# Power.net
KiCad netlist of a schematic drawn in Altium Designer
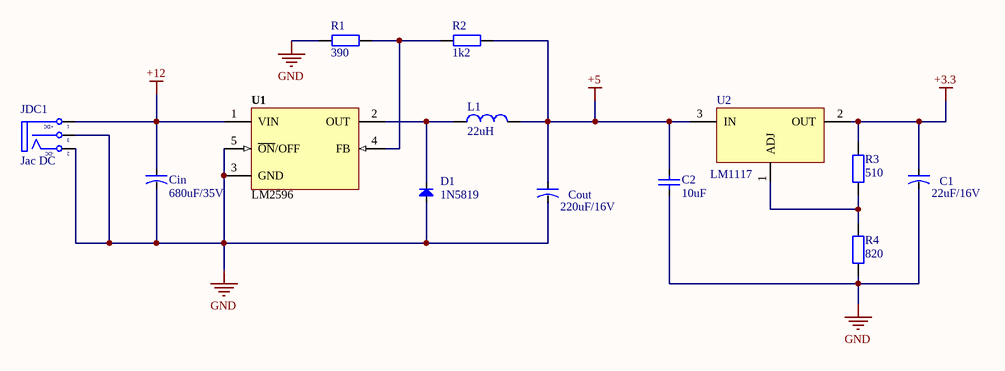
[diagram p0: Power.SchDoc]

(export (version "E")
  (design (tool "Eeschema 10.0.6"))
  (components
    (comp (ref "C1")
      (value "22uF/16V")
      (footprint "CA-ALU-4")
      (description "Capacitor (Semiconductor SIM Model)")
      (fields (field (name "PUBLISHER") "Altium Limited"))
      (libsource (lib "My Library") (part "CAP-ALU-DIP"))
    )
    (comp (ref "C2")
      (value "10uF")
      (footprint "CAP_0805")
      (description "Capacitor")
      (fields (field (name "PUBLISHER") "Altium Limited"))
      (libsource (lib "My Library") (part "CapSMD"))
    )
    (comp (ref "Cin")
      (value "680uF/35V")
      (footprint "CA-ALU-10")
      (description "Capacitor (Semiconductor SIM Model)")
      (fields (field (name "PUBLISHER") "Altium Limited"))
      (libsource (lib "My Library") (part "CAP-ALU-DIP"))
    )
    (comp (ref "Cout")
      (value "220uF/16V")
      (footprint "CA-ALU-6.3")
      (description "Capacitor (Semiconductor SIM Model)")
      (fields (field (name "PUBLISHER") "Altium Limited"))
      (libsource (lib "My Library") (part "CAP-ALU-DIP"))
    )
    (comp (ref "D1")
      (value "1N5819")
      (footprint "SMA")
      (description "Default Diode")
      (fields (field (name "PUBLISHER") "Altium Limited"))
      (libsource (lib "My Library") (part "Diode"))
    )
    (comp (ref "JDC1")
      (value "Jac DC")
      (footprint "DC-IN")
      (description "Jac DC input")
      (libsource (lib "My Library") (part "DCIN"))
    )
    (comp (ref "L1")
      (value "22uH")
      (footprint "L-SMD-M-12x10")
      (description "Inductor")
      (libsource (lib "My Library") (part "Inductor"))
    )
    (comp (ref "R1")
      (value "390")
      (footprint "RES-SMD-0805")
      (description "Resistor SMD")
      (fields
        (field (name "MANUFACTURER") "Generic Components")
        (field (name "PUBLISHER") "Altium Hobart Technology Centre")
      )
      (libsource (lib "My Library") (part "Resistor - SMD"))
    )
    (comp (ref "R2")
      (value "1k2")
      (footprint "RES-SMD-0805")
      (description "Resistor SMD")
      (fields
        (field (name "MANUFACTURER") "Generic Components")
        (field (name "PUBLISHER") "Altium Hobart Technology Centre")
      )
      (libsource (lib "My Library") (part "Resistor - SMD"))
    )
    (comp (ref "R3")
      (value "510")
      (footprint "RES-SMD-0805")
      (description "Resistor SMD")
      (fields
        (field (name "MANUFACTURER") "Generic Components")
        (field (name "PUBLISHER") "Altium Hobart Technology Centre")
      )
      (libsource (lib "My Library") (part "Resistor - SMD"))
    )
    (comp (ref "R4")
      (value "820")
      (footprint "RES-SMD-0805")
      (description "Resistor SMD")
      (fields
        (field (name "MANUFACTURER") "Generic Components")
        (field (name "PUBLISHER") "Altium Hobart Technology Centre")
      )
      (libsource (lib "My Library") (part "Resistor - SMD"))
    )
    (comp (ref "U1") (value "LM2596") (footprint "TO-263") (libsource (lib "My Library") (part "LM2596")))
    (comp (ref "U2")
      (value "LM1117")
      (footprint "LM1117-SOP")
      (description "800mA Low-Dropout Linear Regulator")
      (fields (field (name "CREATOR") "Nguyen Ba Bien"))
      (libsource (lib "My Library") (part "LM1117-ADJ"))
    )
  )
  (nets
    (net (code "1") (name "+3.3") (class "Default")
      (node (ref "C1") (pin "1") (pinfunction "1_1") (pintype "passive"))
      (node (ref "R3") (pin "1") (pinfunction "1_1") (pintype "passive"))
      (node (ref "U2") (pin "2") (pinfunction "OUT_2") (pintype "passive"))
    )
    (net (code "2") (name "+5") (class "Default")
      (node (ref "C2") (pin "2") (pinfunction "2_2") (pintype "passive"))
      (node (ref "Cout") (pin "1") (pinfunction "1_1") (pintype "passive"))
      (node (ref "L1") (pin "2") (pinfunction "2_2") (pintype "passive"))
      (node (ref "R2") (pin "1") (pinfunction "1_1") (pintype "passive"))
      (node (ref "U2") (pin "3") (pinfunction "IN_3") (pintype "passive"))
    )
    (net (code "3") (name "+12") (class "Default")
      (node (ref "Cin") (pin "1") (pinfunction "1_1") (pintype "passive"))
      (node (ref "JDC1") (pin "1") (pinfunction "T_1") (pintype "passive"))
      (node (ref "U1") (pin "1") (pinfunction "VIN_1") (pintype "power_in"))
    )
    (net (code "4") (name "GND") (class "Default")
      (node (ref "C1") (pin "2") (pinfunction "2_2") (pintype "passive"))
      (node (ref "C2") (pin "1") (pinfunction "1_1") (pintype "passive"))
      (node (ref "Cin") (pin "2") (pinfunction "2_2") (pintype "passive"))
      (node (ref "Cout") (pin "2") (pinfunction "2_2") (pintype "passive"))
      (node (ref "D1") (pin "1") (pinfunction "A_1") (pintype "passive"))
      (node (ref "JDC1") (pin "2") (pinfunction "TN_2") (pintype "passive"))
      (node (ref "JDC1") (pin "3") (pinfunction "S_3") (pintype "power_in"))
      (node (ref "R1") (pin "2") (pinfunction "2_2") (pintype "passive"))
      (node (ref "R4") (pin "2") (pinfunction "2_2") (pintype "passive"))
      (node (ref "U1") (pin "3") (pinfunction "GND_3") (pintype "power_in"))
      (node (ref "U1") (pin "5") (pinfunction "~{ON}/OFF_5") (pintype "input"))
    )
    (net (code "5") (name "Net-(D1-K)") (class "Default")
      (node (ref "D1") (pin "2") (pinfunction "K_2") (pintype "passive"))
      (node (ref "L1") (pin "1") (pinfunction "1_1") (pintype "passive"))
      (node (ref "U1") (pin "2") (pinfunction "OUT_2") (pintype "power_in"))
    )
    (net (code "6") (name "Net-(U1-FB)") (class "Default")
      (node (ref "R1") (pin "1") (pinfunction "1_1") (pintype "passive"))
      (node (ref "R2") (pin "2") (pinfunction "2_2") (pintype "passive"))
      (node (ref "U1") (pin "4") (pinfunction "FB_4") (pintype "input"))
    )
    (net (code "7") (name "Net-(U2-ADJ)") (class "Default")
      (node (ref "R3") (pin "2") (pinfunction "2_2") (pintype "passive"))
      (node (ref "R4") (pin "1") (pinfunction "1_1") (pintype "passive"))
      (node (ref "U2") (pin "1") (pinfunction "ADJ_1") (pintype "passive"))
    )
  )
)
